# FlightComputer.net
KiCad netlist of a schematic drawn in Altium Designer
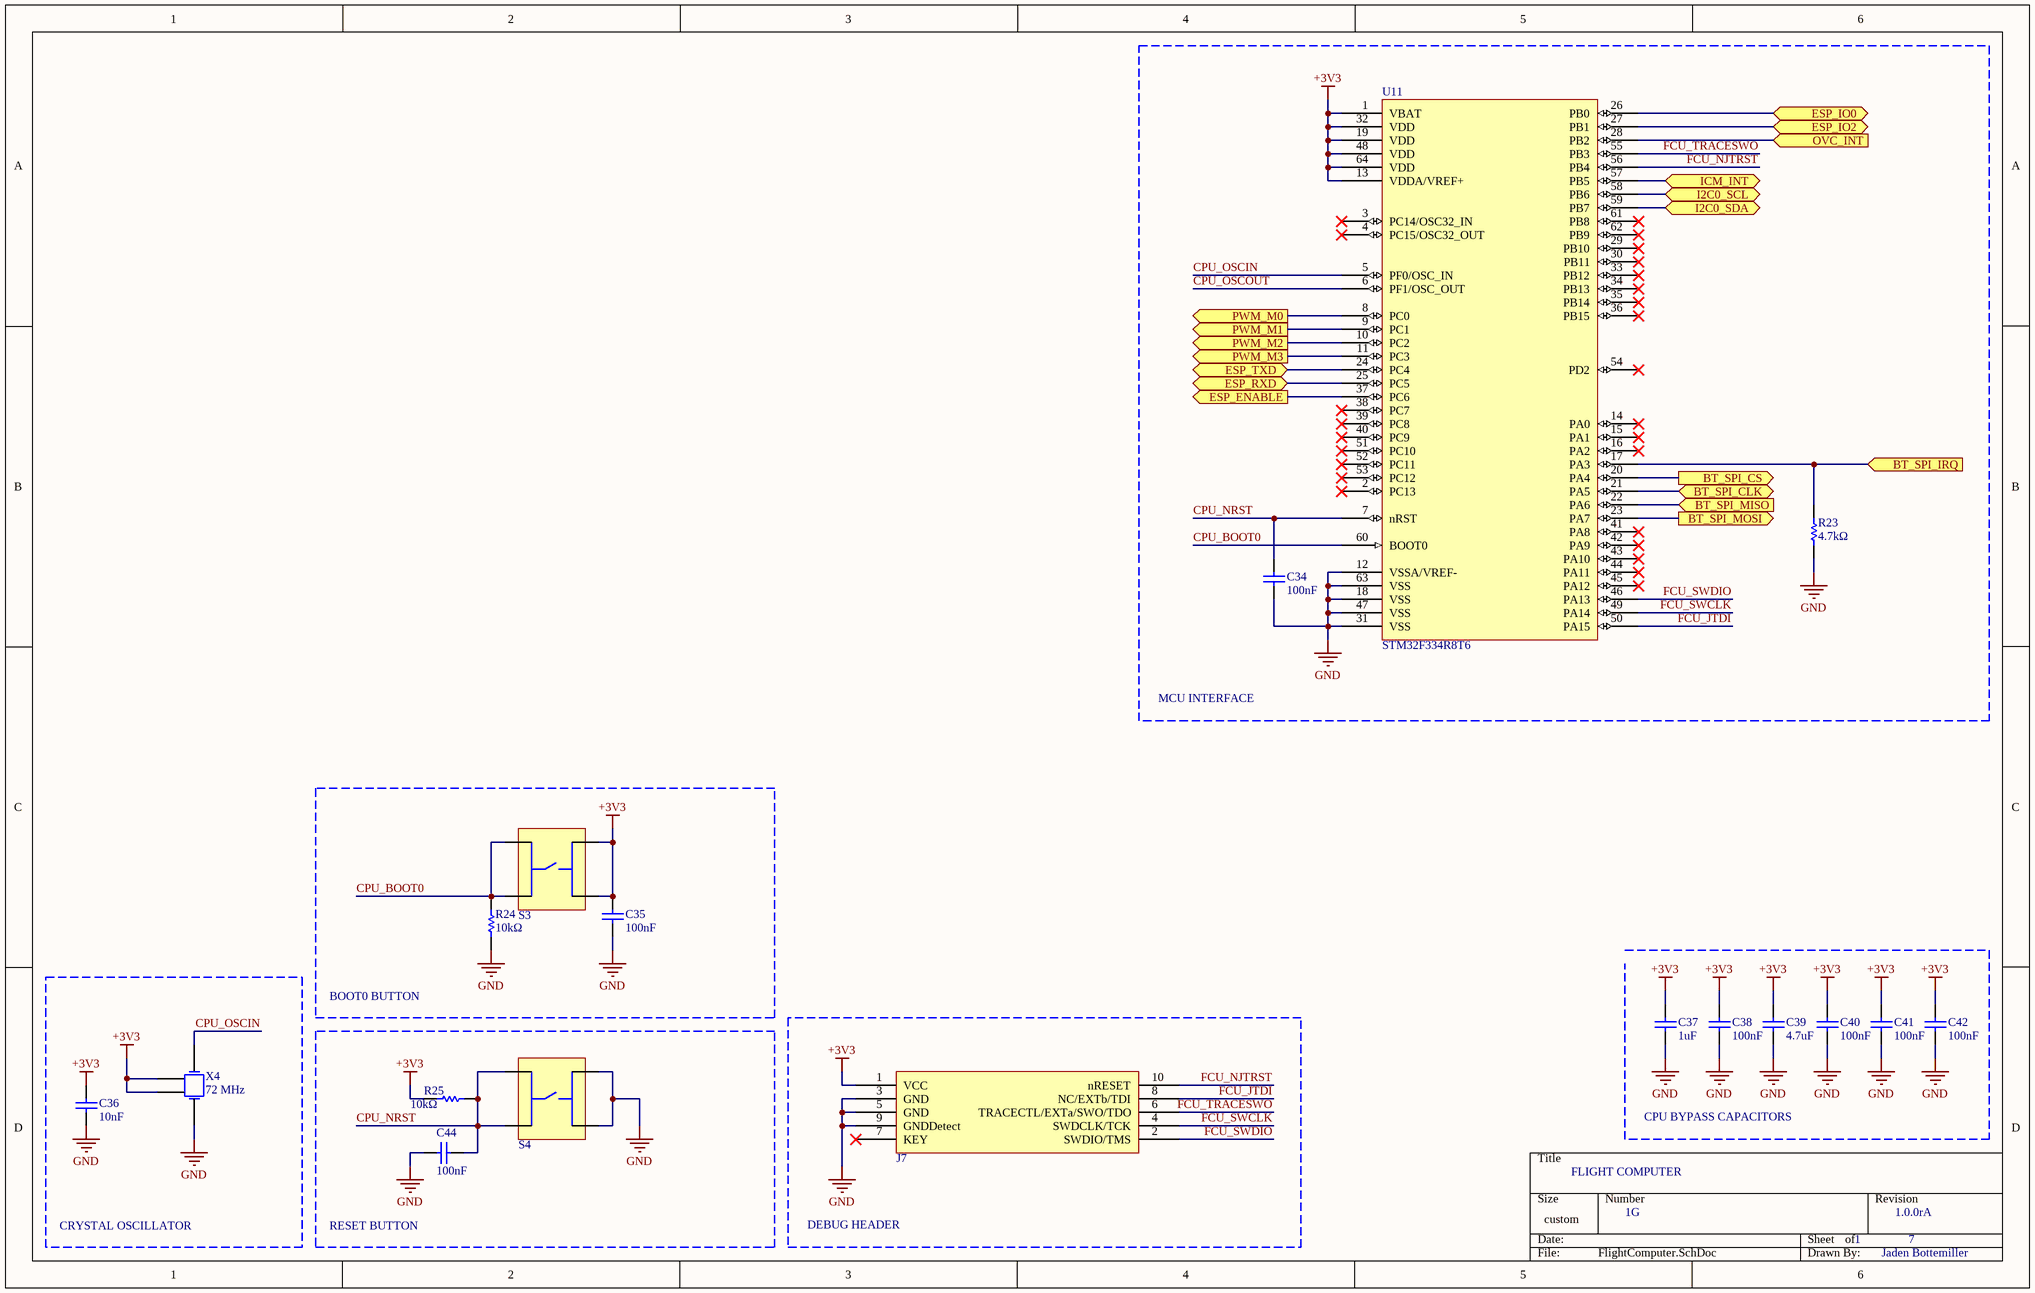
[diagram p0: FlightComputer.SchDoc]

(export (version "E")
  (design (tool "Eeschema 10.0.6"))
  (components
    (comp (ref "C34")
      (value "100nF")
      (description "Standard Capacitor")
      (fields (field (name "Comment") "CAP"))
      (libsource (lib "NikoboticsLib") (part "CAP"))
    )
    (comp (ref "C35")
      (value "100nF")
      (description "Standard Capacitor")
      (fields (field (name "Comment") "CAP"))
      (libsource (lib "NikoboticsLib") (part "CAP"))
    )
    (comp (ref "C36")
      (value "10nF")
      (description "Standard Capacitor")
      (fields (field (name "Comment") "CAP"))
      (libsource (lib "NikoboticsLib") (part "CAP"))
    )
    (comp (ref "C37")
      (value "1uF")
      (description "Standard Capacitor")
      (fields (field (name "Comment") "CAP"))
      (libsource (lib "NikoboticsLib") (part "CAP"))
    )
    (comp (ref "C38")
      (value "100nF")
      (description "Standard Capacitor")
      (fields (field (name "Comment") "CAP"))
      (libsource (lib "NikoboticsLib") (part "CAP"))
    )
    (comp (ref "C39")
      (value "4.7uF")
      (description "Standard Capacitor")
      (fields (field (name "Comment") "CAP"))
      (libsource (lib "NikoboticsLib") (part "CAP"))
    )
    (comp (ref "C40")
      (value "100nF")
      (description "Standard Capacitor")
      (fields (field (name "Comment") "CAP"))
      (libsource (lib "NikoboticsLib") (part "CAP"))
    )
    (comp (ref "C41")
      (value "100nF")
      (description "Standard Capacitor")
      (fields (field (name "Comment") "CAP"))
      (libsource (lib "NikoboticsLib") (part "CAP"))
    )
    (comp (ref "C42")
      (value "100nF")
      (description "Standard Capacitor")
      (fields (field (name "Comment") "CAP"))
      (libsource (lib "NikoboticsLib") (part "CAP"))
    )
    (comp (ref "C44")
      (value "100nF")
      (description "Standard Capacitor")
      (fields (field (name "Comment") "CAP"))
      (libsource (lib "NikoboticsLib") (part "CAP"))
    )
    (comp (ref "J7")
      (value "Debug Connector")
      (description "10-Pin Cortex-M Debug Connector")
      (libsource (lib "NikoboticsLib") (part "Cortex-M Debug"))
    )
    (comp (ref "R23")
      (value "4.7kΩ")
      (description "Standard Resistor")
      (fields (field (name "Comment") "RES"))
      (libsource (lib "NikoboticsLib") (part "RES"))
    )
    (comp (ref "R24")
      (value "10kΩ")
      (description "Standard Resistor")
      (fields (field (name "Comment") "RES"))
      (libsource (lib "NikoboticsLib") (part "RES"))
    )
    (comp (ref "R25")
      (value "10kΩ")
      (description "Standard Resistor")
      (fields (field (name "Comment") "RES"))
      (libsource (lib "NikoboticsLib") (part "RES"))
    )
    (comp (ref "S3")
      (value "Pushbutton")
      (description "Standard Pushbutton with 4 Terminals")
      (libsource (lib "NikoboticsLib") (part "PUSHBTN_4T"))
    )
    (comp (ref "S4")
      (value "Pushbutton")
      (description "Standard Pushbutton with 4 Terminals")
      (libsource (lib "NikoboticsLib") (part "PUSHBTN_4T"))
    )
    (comp (ref "U11")
      (value "STM32F334R8T6")
      (description "ARM® Cortex®-M4 STM32F3 Microcontroller IC 32-Bit 72MHz 64KB (64K x 8) FLASH 64-LQFP (10x10)")
      (libsource (lib "NikoboticsLib") (part "STM32F334R8T6"))
    )
    (comp (ref "X4")
      (value "72 MHz")
      (description "Standard Crystal Oscillator with two ground connections.")
      (fields (field (name "Comment") "Crystal Oscillator"))
      (libsource (lib "NikoboticsLib") (part "OSC_2GND"))
    )
  )
  (nets
    (net (code "1") (name "+3V3") (class "Default")
      (node (ref "C35") (pin "1") (pinfunction "1_1") (pintype "passive"))
      (node (ref "C36") (pin "1") (pinfunction "1_1") (pintype "passive"))
      (node (ref "C37") (pin "2") (pinfunction "2_2") (pintype "passive"))
      (node (ref "C38") (pin "2") (pinfunction "2_2") (pintype "passive"))
      (node (ref "C39") (pin "2") (pinfunction "2_2") (pintype "passive"))
      (node (ref "C40") (pin "2") (pinfunction "2_2") (pintype "passive"))
      (node (ref "C41") (pin "2") (pinfunction "2_2") (pintype "passive"))
      (node (ref "C42") (pin "2") (pinfunction "2_2") (pintype "passive"))
      (node (ref "J7") (pin "1") (pinfunction "VCC_1") (pintype "power_in"))
      (node (ref "R25") (pin "1") (pinfunction "1_1") (pintype "passive"))
      (node (ref "S3") (pin "3") (pinfunction "Pin_3") (pintype "passive"))
      (node (ref "S3") (pin "4") (pinfunction "Pin_4") (pintype "passive"))
      (node (ref "U11") (pin "1") (pinfunction "VBAT_1") (pintype "power_in"))
      (node (ref "U11") (pin "13") (pinfunction "VDDA/VREF+_13") (pintype "power_in"))
      (node (ref "U11") (pin "19") (pinfunction "VDD_19") (pintype "power_in"))
      (node (ref "U11") (pin "32") (pinfunction "VDD_32") (pintype "power_in"))
      (node (ref "U11") (pin "48") (pinfunction "VDD_48") (pintype "power_in"))
      (node (ref "U11") (pin "64") (pinfunction "VDD_64") (pintype "power_in"))
      (node (ref "X4") (pin "2") (pinfunction "GND_2") (pintype "passive"))
      (node (ref "X4") (pin "4") (pinfunction "GND_4") (pintype "passive"))
    )
    (net (code "2") (name "/BT_SPI_CLK") (class "Default")
      (node (ref "U11") (pin "21") (pinfunction "PA5_21") (pintype "bidirectional"))
    )
    (net (code "3") (name "/BT_SPI_CS") (class "Default")
      (node (ref "U11") (pin "20") (pinfunction "PA4_20") (pintype "bidirectional"))
    )
    (net (code "4") (name "/BT_SPI_IRQ") (class "Default")
      (node (ref "R23") (pin "2") (pinfunction "2_2") (pintype "passive"))
      (node (ref "U11") (pin "17") (pinfunction "PA3_17") (pintype "bidirectional"))
    )
    (net (code "5") (name "/BT_SPI_MISO") (class "Default")
      (node (ref "U11") (pin "22") (pinfunction "PA6_22") (pintype "bidirectional"))
    )
    (net (code "6") (name "/BT_SPI_MOSI") (class "Default")
      (node (ref "U11") (pin "23") (pinfunction "PA7_23") (pintype "bidirectional"))
    )
    (net (code "7") (name "/CPU_BOOT0") (class "Default")
      (node (ref "R24") (pin "2") (pinfunction "2_2") (pintype "passive"))
      (node (ref "S3") (pin "1") (pintype "passive"))
      (node (ref "S3") (pin "2") (pinfunction "Pin_2") (pintype "passive"))
      (node (ref "U11") (pin "60") (pinfunction "BOOT0_60") (pintype "input"))
    )
    (net (code "8") (name "/CPU_NRST") (class "Default")
      (node (ref "C34") (pin "2") (pinfunction "2_2") (pintype "passive"))
      (node (ref "C44") (pin "1") (pinfunction "1_1") (pintype "passive"))
      (node (ref "R25") (pin "2") (pinfunction "2_2") (pintype "passive"))
      (node (ref "S4") (pin "1") (pintype "passive"))
      (node (ref "S4") (pin "2") (pinfunction "Pin_2") (pintype "passive"))
      (node (ref "U11") (pin "7") (pinfunction "nRST_7") (pintype "bidirectional"))
    )
    (net (code "9") (name "/CPU_OSCIN") (class "Default")
      (node (ref "U11") (pin "5") (pinfunction "PF0/OSC_IN_5") (pintype "bidirectional"))
      (node (ref "X4") (pin "1") (pinfunction "X1_1") (pintype "passive"))
    )
    (net (code "10") (name "/CPU_OSCOUT") (class "Default")
      (node (ref "U11") (pin "6") (pinfunction "PF1/OSC_OUT_6") (pintype "bidirectional"))
    )
    (net (code "11") (name "/ESP_ENABLE") (class "Default")
      (node (ref "U11") (pin "37") (pinfunction "PC6_37") (pintype "bidirectional"))
    )
    (net (code "12") (name "/ESP_IO0") (class "Default")
      (node (ref "U11") (pin "26") (pinfunction "PB0_26") (pintype "bidirectional"))
    )
    (net (code "13") (name "/ESP_IO2") (class "Default")
      (node (ref "U11") (pin "27") (pinfunction "PB1_27") (pintype "bidirectional"))
    )
    (net (code "14") (name "/ESP_RXD") (class "Default")
      (node (ref "U11") (pin "25") (pinfunction "PC5_25") (pintype "bidirectional"))
    )
    (net (code "15") (name "/ESP_TXD") (class "Default")
      (node (ref "U11") (pin "24") (pinfunction "PC4_24") (pintype "bidirectional"))
    )
    (net (code "16") (name "/FCU_JTDI") (class "Default")
      (node (ref "J7") (pin "8") (pinfunction "NC/EXTb/TDI_8") (pintype "passive"))
      (node (ref "U11") (pin "50") (pinfunction "PA15_50") (pintype "bidirectional"))
    )
    (net (code "17") (name "/FCU_NJTRST") (class "Default")
      (node (ref "J7") (pin "10") (pinfunction "nRESET_10") (pintype "passive"))
      (node (ref "U11") (pin "56") (pinfunction "PB4_56") (pintype "bidirectional"))
    )
    (net (code "18") (name "/FCU_SWCLK") (class "Default")
      (node (ref "J7") (pin "4") (pinfunction "SWDCLK/TCK_4") (pintype "passive"))
      (node (ref "U11") (pin "49") (pinfunction "PA14_49") (pintype "bidirectional"))
    )
    (net (code "19") (name "/FCU_SWDIO") (class "Default")
      (node (ref "J7") (pin "2") (pinfunction "SWDIO/TMS_2") (pintype "passive"))
      (node (ref "U11") (pin "46") (pinfunction "PA13_46") (pintype "bidirectional"))
    )
    (net (code "20") (name "/FCU_TRACESWO") (class "Default")
      (node (ref "J7") (pin "6") (pinfunction "TRACECTL/EXTa/SWO/TDO_6") (pintype "passive"))
      (node (ref "U11") (pin "55") (pinfunction "PB3_55") (pintype "bidirectional"))
    )
    (net (code "21") (name "/I2C0_SCL") (class "Default")
      (node (ref "U11") (pin "58") (pinfunction "PB6_58") (pintype "bidirectional"))
    )
    (net (code "22") (name "/I2C0_SDA") (class "Default")
      (node (ref "U11") (pin "59") (pinfunction "PB7_59") (pintype "bidirectional"))
    )
    (net (code "23") (name "/ICM_INT") (class "Default")
      (node (ref "U11") (pin "57") (pinfunction "PB5_57") (pintype "bidirectional"))
    )
    (net (code "24") (name "/OVC_INT") (class "Default")
      (node (ref "U11") (pin "28") (pinfunction "PB2_28") (pintype "bidirectional"))
    )
    (net (code "25") (name "/PWM_M0") (class "Default")
      (node (ref "U11") (pin "8") (pinfunction "PC0_8") (pintype "bidirectional"))
    )
    (net (code "26") (name "/PWM_M1") (class "Default")
      (node (ref "U11") (pin "9") (pinfunction "PC1_9") (pintype "bidirectional"))
    )
    (net (code "27") (name "/PWM_M2") (class "Default")
      (node (ref "U11") (pin "10") (pinfunction "PC2_10") (pintype "bidirectional"))
    )
    (net (code "28") (name "/PWM_M3") (class "Default")
      (node (ref "U11") (pin "11") (pinfunction "PC3_11") (pintype "bidirectional"))
    )
    (net (code "29") (name "GND") (class "Default")
      (node (ref "C34") (pin "1") (pinfunction "1_1") (pintype "passive"))
      (node (ref "C35") (pin "2") (pinfunction "2_2") (pintype "passive"))
      (node (ref "C36") (pin "2") (pinfunction "2_2") (pintype "passive"))
      (node (ref "C37") (pin "1") (pinfunction "1_1") (pintype "passive"))
      (node (ref "C38") (pin "1") (pinfunction "1_1") (pintype "passive"))
      (node (ref "C39") (pin "1") (pinfunction "1_1") (pintype "passive"))
      (node (ref "C40") (pin "1") (pinfunction "1_1") (pintype "passive"))
      (node (ref "C41") (pin "1") (pinfunction "1_1") (pintype "passive"))
      (node (ref "C42") (pin "1") (pinfunction "1_1") (pintype "passive"))
      (node (ref "C44") (pin "2") (pinfunction "2_2") (pintype "passive"))
      (node (ref "J7") (pin "3") (pinfunction "GND_3") (pintype "power_in"))
      (node (ref "J7") (pin "5") (pinfunction "GND_5") (pintype "power_in"))
      (node (ref "J7") (pin "9") (pinfunction "GNDDetect_9") (pintype "power_in"))
      (node (ref "R23") (pin "1") (pinfunction "1_1") (pintype "passive"))
      (node (ref "R24") (pin "1") (pinfunction "1_1") (pintype "passive"))
      (node (ref "S4") (pin "3") (pinfunction "Pin_3") (pintype "passive"))
      (node (ref "S4") (pin "4") (pinfunction "Pin_4") (pintype "passive"))
      (node (ref "U11") (pin "12") (pinfunction "VSSA/VREF-_12") (pintype "power_in"))
      (node (ref "U11") (pin "18") (pinfunction "VSS_18") (pintype "power_in"))
      (node (ref "U11") (pin "31") (pinfunction "VSS_31") (pintype "power_in"))
      (node (ref "U11") (pin "47") (pinfunction "VSS_47") (pintype "power_in"))
      (node (ref "U11") (pin "63") (pinfunction "VSS_63") (pintype "power_in"))
      (node (ref "X4") (pin "3") (pinfunction "X2_3") (pintype "passive"))
    )
    (net (code "30") (name "unconnected-(J7-KEY-Pad7)") (class "Default")
      (node (ref "J7") (pin "7") (pinfunction "KEY_7") (pintype "passive+no_connect"))
    )
    (net (code "31") (name "unconnected-(U11-PA0-Pad14)") (class "Default")
      (node (ref "U11") (pin "14") (pinfunction "PA0_14") (pintype "bidirectional+no_connect"))
    )
    (net (code "32") (name "unconnected-(U11-PA1-Pad15)") (class "Default")
      (node (ref "U11") (pin "15") (pinfunction "PA1_15") (pintype "bidirectional+no_connect"))
    )
    (net (code "33") (name "unconnected-(U11-PA2-Pad16)") (class "Default")
      (node (ref "U11") (pin "16") (pinfunction "PA2_16") (pintype "bidirectional+no_connect"))
    )
    (net (code "34") (name "unconnected-(U11-PA8-Pad41)") (class "Default")
      (node (ref "U11") (pin "41") (pinfunction "PA8_41") (pintype "bidirectional+no_connect"))
    )
    (net (code "35") (name "unconnected-(U11-PA9-Pad42)") (class "Default")
      (node (ref "U11") (pin "42") (pinfunction "PA9_42") (pintype "bidirectional+no_connect"))
    )
    (net (code "36") (name "unconnected-(U11-PA10-Pad43)") (class "Default")
      (node (ref "U11") (pin "43") (pinfunction "PA10_43") (pintype "bidirectional+no_connect"))
    )
    (net (code "37") (name "unconnected-(U11-PA11-Pad44)") (class "Default")
      (node (ref "U11") (pin "44") (pinfunction "PA11_44") (pintype "bidirectional+no_connect"))
    )
    (net (code "38") (name "unconnected-(U11-PA12-Pad45)") (class "Default")
      (node (ref "U11") (pin "45") (pinfunction "PA12_45") (pintype "bidirectional+no_connect"))
    )
    (net (code "39") (name "unconnected-(U11-PB8-Pad61)") (class "Default")
      (node (ref "U11") (pin "61") (pinfunction "PB8_61") (pintype "bidirectional+no_connect"))
    )
    (net (code "40") (name "unconnected-(U11-PB9-Pad62)") (class "Default")
      (node (ref "U11") (pin "62") (pinfunction "PB9_62") (pintype "bidirectional+no_connect"))
    )
    (net (code "41") (name "unconnected-(U11-PB10-Pad29)") (class "Default")
      (node (ref "U11") (pin "29") (pinfunction "PB10_29") (pintype "bidirectional+no_connect"))
    )
    (net (code "42") (name "unconnected-(U11-PB11-Pad30)") (class "Default")
      (node (ref "U11") (pin "30") (pinfunction "PB11_30") (pintype "bidirectional+no_connect"))
    )
    (net (code "43") (name "unconnected-(U11-PB12-Pad33)") (class "Default")
      (node (ref "U11") (pin "33") (pinfunction "PB12_33") (pintype "bidirectional+no_connect"))
    )
    (net (code "44") (name "unconnected-(U11-PB13-Pad34)") (class "Default")
      (node (ref "U11") (pin "34") (pinfunction "PB13_34") (pintype "bidirectional+no_connect"))
    )
    (net (code "45") (name "unconnected-(U11-PB14-Pad35)") (class "Default")
      (node (ref "U11") (pin "35") (pinfunction "PB14_35") (pintype "bidirectional+no_connect"))
    )
    (net (code "46") (name "unconnected-(U11-PB15-Pad36)") (class "Default")
      (node (ref "U11") (pin "36") (pinfunction "PB15_36") (pintype "bidirectional+no_connect"))
    )
    (net (code "47") (name "unconnected-(U11-PC7-Pad38)") (class "Default")
      (node (ref "U11") (pin "38") (pinfunction "PC7_38") (pintype "bidirectional+no_connect"))
    )
    (net (code "48") (name "unconnected-(U11-PC8-Pad39)") (class "Default")
      (node (ref "U11") (pin "39") (pinfunction "PC8_39") (pintype "bidirectional+no_connect"))
    )
    (net (code "49") (name "unconnected-(U11-PC9-Pad40)") (class "Default")
      (node (ref "U11") (pin "40") (pinfunction "PC9_40") (pintype "bidirectional+no_connect"))
    )
    (net (code "50") (name "unconnected-(U11-PC10-Pad51)") (class "Default")
      (node (ref "U11") (pin "51") (pinfunction "PC10_51") (pintype "bidirectional+no_connect"))
    )
    (net (code "51") (name "unconnected-(U11-PC11-Pad52)") (class "Default")
      (node (ref "U11") (pin "52") (pinfunction "PC11_52") (pintype "bidirectional+no_connect"))
    )
    (net (code "52") (name "unconnected-(U11-PC12-Pad53)") (class "Default")
      (node (ref "U11") (pin "53") (pinfunction "PC12_53") (pintype "bidirectional+no_connect"))
    )
    (net (code "53") (name "unconnected-(U11-PC13-Pad2)") (class "Default")
      (node (ref "U11") (pin "2") (pinfunction "PC13_2") (pintype "bidirectional+no_connect"))
    )
    (net (code "54") (name "unconnected-(U11-PC14{slash}OSC32_IN-Pad3)") (class "Default")
      (node (ref "U11") (pin "3") (pinfunction "PC14/OSC32_IN_3") (pintype "bidirectional+no_connect"))
    )
    (net (code "55") (name "unconnected-(U11-PC15{slash}OSC32_OUT-Pad4)") (class "Default")
      (node (ref "U11") (pin "4") (pinfunction "PC15/OSC32_OUT_4") (pintype "bidirectional+no_connect"))
    )
    (net (code "56") (name "unconnected-(U11-PD2-Pad54)") (class "Default")
      (node (ref "U11") (pin "54") (pinfunction "PD2_54") (pintype "bidirectional+no_connect"))
    )
  )
)
